# cymometer.net
KiCad netlist of a schematic drawn in Altium Designer
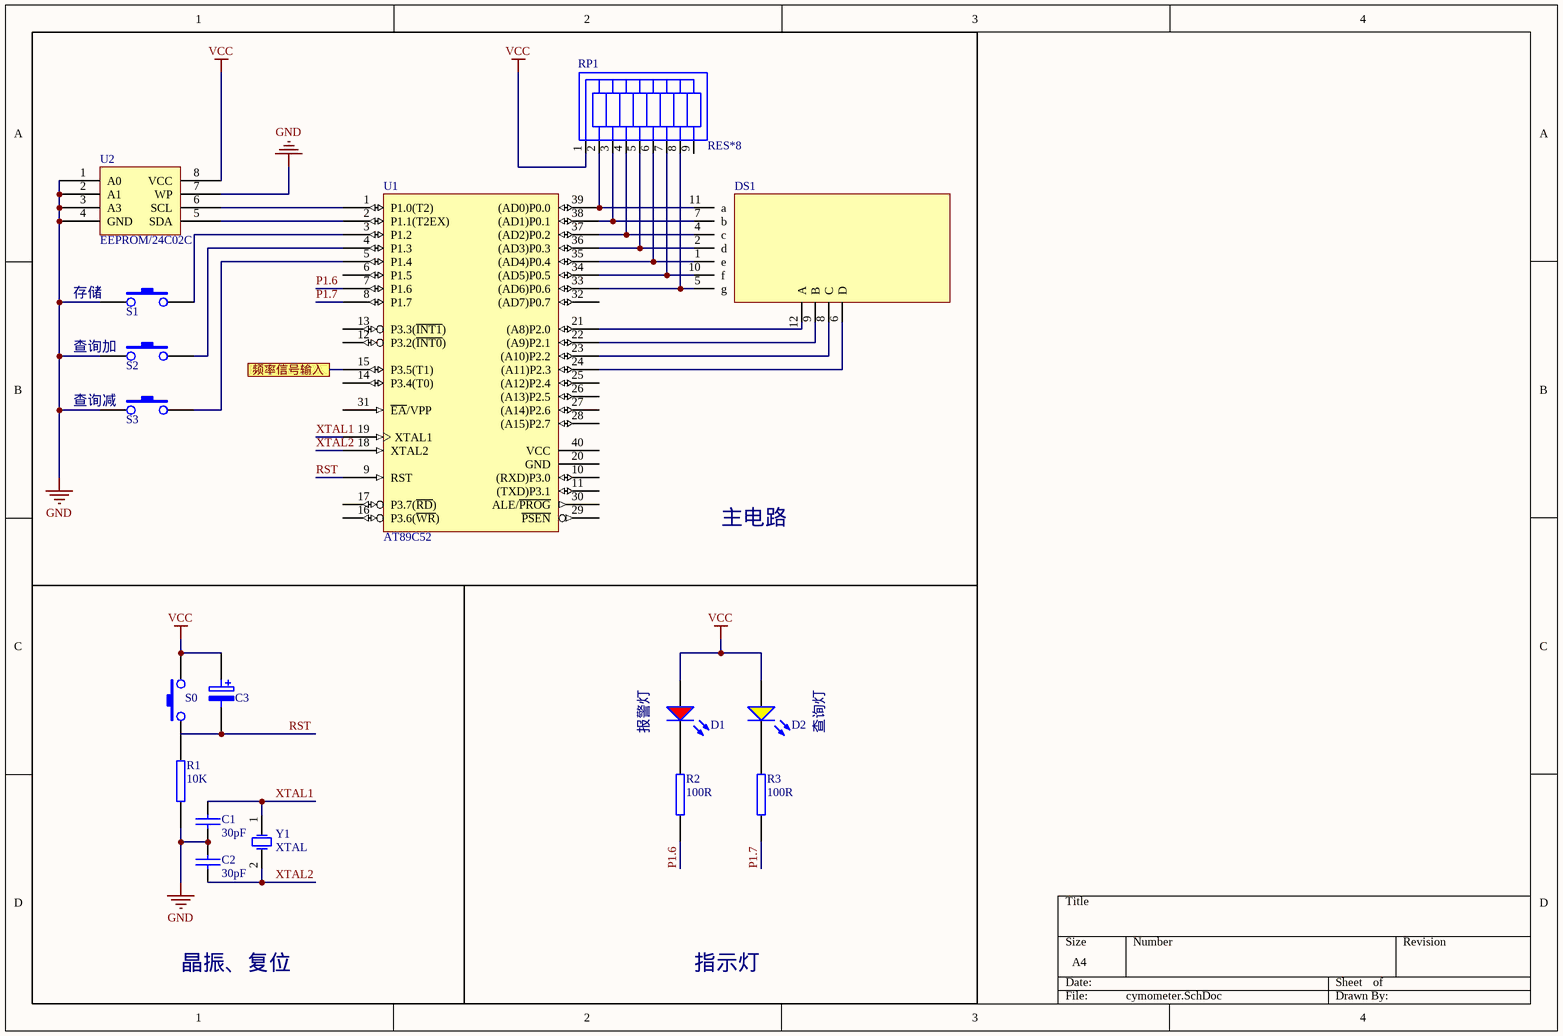
[diagram p0: cymometer.SchDoc]

(export (version "E")
  (design (tool "Eeschema 10.0.6"))
  (components
    (comp (ref "C1") (value "30pF") (description "Capacitor") (libsource (lib "杂元件库") (part "CAP")))
    (comp (ref "C2") (value "30pF") (description "Capacitor") (libsource (lib "杂元件库") (part "CAP")))
    (comp (ref "C3")
      (value "ELECTRO2")
      (description "Electrolytic Capacitor")
      (libsource (lib "杂元件库") (part "ELECTRO2"))
    )
    (comp (ref "D1")
      (value "红灯 0805")
      (footprint "LC-0805_LED_S1")
      (description "发光二极管")
      (libsource (lib "Miscellaneous Devices LC") (part "0805 红灯"))
    )
    (comp (ref "D2")
      (value "黄灯 0805")
      (footprint "LC-0805_LED_S1")
      (description "发光二极管")
      (libsource (lib "Miscellaneous Devices LC") (part "0805 黄灯"))
    )
    (comp (ref "DS1") (value "LED") (footprint "LED-4 - duplicate") (libsource (lib "led数码管") (part "LED-4")))
    (comp (ref "R1") (value "10K") (libsource (lib "杂元件库") (part "RES2")))
    (comp (ref "R2") (value "100R") (libsource (lib "杂元件库") (part "RES2")))
    (comp (ref "R3") (value "100R") (libsource (lib "杂元件库") (part "RES2")))
    (comp (ref "RP1") (value "RES*8") (footprint "SIP9") (libsource (lib "常用1") (part "RES*8")))
    (comp (ref "S0") (value "SW-PB") (libsource (lib "杂元件库") (part "SW-PB")))
    (comp (ref "S1") (value "SW-PB") (libsource (lib "杂元件库") (part "SW-PB")))
    (comp (ref "S2") (value "SW-PB") (libsource (lib "杂元件库") (part "SW-PB")))
    (comp (ref "S3") (value "SW-PB") (libsource (lib "杂元件库") (part "SW-PB")))
    (comp (ref "U1")
      (value "AT89C52")
      (footprint "Dual-In-Line Package:DIP-40")
      (description "8-Bit Microcontroller with 8K Flash ROM")
      (libsource (lib "Atmel Microcontroller 8051 Architecture") (part "AT89C52"))
    )
    (comp (ref "U2")
      (value "EEPROM/24C02C")
      (footprint "LC-SOIC-8_150mil")
      (description "EEPROM")
      (libsource (lib "Miscellaneous Devices LC") (part "EEPROM/AT24C256C-SSHL-T"))
    )
    (comp (ref "Y1") (value "XTAL") (footprint "XTAL") (libsource (lib "XTAL") (part "XTAL")))
  )
  (nets
    (net (code "1") (name "/P1.6") (class "Default")
      (node (ref "R2") (pin "2") (pinfunction "2_2") (pintype "passive"))
      (node (ref "U1") (pin "7") (pinfunction "P1.6_7") (pintype "bidirectional"))
    )
    (net (code "2") (name "/P1.7") (class "Default")
      (node (ref "R3") (pin "2") (pinfunction "2_2") (pintype "passive"))
      (node (ref "U1") (pin "8") (pinfunction "P1.7_8") (pintype "bidirectional"))
    )
    (net (code "3") (name "/RST") (class "Default")
      (node (ref "C3") (pin "2") (pinfunction "2_2") (pintype "passive"))
      (node (ref "R1") (pin "1") (pinfunction "1_1") (pintype "passive"))
      (node (ref "U1") (pin "9") (pinfunction "RST_9") (pintype "input"))
    )
    (net (code "4") (name "/XTAL1") (class "Default")
      (node (ref "C1") (pin "1") (pinfunction "1_1") (pintype "passive"))
      (node (ref "U1") (pin "19") (pinfunction "XTAL1_19") (pintype "input"))
      (node (ref "Y1") (pin "1") (pinfunction "1_1") (pintype "passive"))
    )
    (net (code "5") (name "/XTAL2") (class "Default")
      (node (ref "C2") (pin "2") (pinfunction "2_2") (pintype "passive"))
      (node (ref "U1") (pin "18") (pinfunction "XTAL2_18") (pintype "input"))
      (node (ref "Y1") (pin "2") (pinfunction "2_2") (pintype "passive"))
    )
    (net (code "6") (name "/频率信号输入") (class "Default")
      (node (ref "U1") (pin "15") (pinfunction "P3.5(T1)_15") (pintype "bidirectional"))
    )
    (net (code "7") (name "GND") (class "Default")
      (node (ref "C1") (pin "2") (pinfunction "2_2") (pintype "passive"))
      (node (ref "C2") (pin "1") (pinfunction "1_1") (pintype "passive"))
      (node (ref "R1") (pin "2") (pinfunction "2_2") (pintype "passive"))
      (node (ref "S1") (pin "2") (pinfunction "2_2") (pintype "passive"))
      (node (ref "S2") (pin "2") (pinfunction "2_2") (pintype "passive"))
      (node (ref "S3") (pin "2") (pinfunction "2_2") (pintype "passive"))
      (node (ref "U2") (pin "1") (pinfunction "A0_1") (pintype "passive"))
      (node (ref "U2") (pin "2") (pinfunction "A1_2") (pintype "passive"))
      (node (ref "U2") (pin "3") (pinfunction "A3_3") (pintype "passive"))
      (node (ref "U2") (pin "4") (pinfunction "GND_4") (pintype "passive"))
      (node (ref "U2") (pin "7") (pinfunction "WP_7") (pintype "passive"))
    )
    (net (code "8") (name "Net-(D1-PadK)") (class "Default")
      (node (ref "D1") (pin "K") (pinfunction "K_K") (pintype "passive"))
      (node (ref "R2") (pin "1") (pinfunction "1_1") (pintype "passive"))
    )
    (net (code "9") (name "Net-(D2-PadK)") (class "Default")
      (node (ref "D2") (pin "K") (pinfunction "K_K") (pintype "passive"))
      (node (ref "R3") (pin "1") (pinfunction "1_1") (pintype "passive"))
    )
    (net (code "10") (name "Net-(DS1-A)") (class "Default")
      (node (ref "DS1") (pin "12") (pinfunction "A_12") (pintype "passive"))
      (node (ref "U1") (pin "21") (pinfunction "(A8)P2.0_21") (pintype "bidirectional"))
    )
    (net (code "11") (name "Net-(DS1-B)") (class "Default")
      (node (ref "DS1") (pin "9") (pinfunction "B_9") (pintype "passive"))
      (node (ref "U1") (pin "22") (pinfunction "(A9)P2.1_22") (pintype "bidirectional"))
    )
    (net (code "12") (name "Net-(DS1-C)") (class "Default")
      (node (ref "DS1") (pin "8") (pinfunction "C_8") (pintype "passive"))
      (node (ref "U1") (pin "23") (pinfunction "(A10)P2.2_23") (pintype "bidirectional"))
    )
    (net (code "13") (name "Net-(DS1-D)") (class "Default")
      (node (ref "DS1") (pin "6") (pinfunction "D_6") (pintype "passive"))
      (node (ref "U1") (pin "24") (pinfunction "(A11)P2.3_24") (pintype "bidirectional"))
    )
    (net (code "14") (name "Net-(DS1-a)") (class "Default")
      (node (ref "DS1") (pin "11") (pinfunction "a_11") (pintype "passive"))
      (node (ref "RP1") (pin "2") (pintype "passive"))
      (node (ref "U1") (pin "39") (pinfunction "(AD0)P0.0_39") (pintype "bidirectional"))
    )
    (net (code "15") (name "Net-(DS1-b)") (class "Default")
      (node (ref "DS1") (pin "7") (pinfunction "b_7") (pintype "passive"))
      (node (ref "RP1") (pin "3") (pintype "passive"))
      (node (ref "U1") (pin "38") (pinfunction "(AD1)P0.1_38") (pintype "bidirectional"))
    )
    (net (code "16") (name "Net-(DS1-c)") (class "Default")
      (node (ref "DS1") (pin "4") (pinfunction "c_4") (pintype "passive"))
      (node (ref "RP1") (pin "4") (pintype "passive"))
      (node (ref "U1") (pin "37") (pinfunction "(AD2)P0.2_37") (pintype "bidirectional"))
    )
    (net (code "17") (name "Net-(DS1-d)") (class "Default")
      (node (ref "DS1") (pin "2") (pinfunction "d_2") (pintype "passive"))
      (node (ref "RP1") (pin "5") (pintype "passive"))
      (node (ref "U1") (pin "36") (pinfunction "(AD3)P0.3_36") (pintype "bidirectional"))
    )
    (net (code "18") (name "Net-(DS1-e)") (class "Default")
      (node (ref "DS1") (pin "1") (pinfunction "e_1") (pintype "passive"))
      (node (ref "RP1") (pin "6") (pintype "passive"))
      (node (ref "U1") (pin "35") (pinfunction "(AD4)P0.4_35") (pintype "bidirectional"))
    )
    (net (code "19") (name "Net-(DS1-f)") (class "Default")
      (node (ref "DS1") (pin "10") (pinfunction "f_10") (pintype "passive"))
      (node (ref "RP1") (pin "7") (pintype "passive"))
      (node (ref "U1") (pin "34") (pinfunction "(AD5)P0.5_34") (pintype "bidirectional"))
    )
    (net (code "20") (name "Net-(DS1-g)") (class "Default")
      (node (ref "DS1") (pin "5") (pinfunction "g_5") (pintype "passive"))
      (node (ref "RP1") (pin "8") (pintype "passive"))
      (node (ref "U1") (pin "33") (pinfunction "(AD6)P0.6_33") (pintype "bidirectional"))
    )
    (net (code "21") (name "Net-(U1-P1.0(T2))") (class "Default")
      (node (ref "U1") (pin "1") (pinfunction "P1.0(T2)_1") (pintype "bidirectional"))
      (node (ref "U2") (pin "6") (pinfunction "SCL_6") (pintype "passive"))
    )
    (net (code "22") (name "Net-(U1-P1.1(T2EX))") (class "Default")
      (node (ref "U1") (pin "2") (pinfunction "P1.1(T2EX)_2") (pintype "bidirectional"))
      (node (ref "U2") (pin "5") (pinfunction "SDA_5") (pintype "passive"))
    )
    (net (code "23") (name "Net-(U1-P1.2)") (class "Default")
      (node (ref "S1") (pin "1") (pinfunction "1_1") (pintype "passive"))
      (node (ref "U1") (pin "3") (pinfunction "P1.2_3") (pintype "bidirectional"))
    )
    (net (code "24") (name "Net-(U1-P1.3)") (class "Default")
      (node (ref "S2") (pin "1") (pinfunction "1_1") (pintype "passive"))
      (node (ref "U1") (pin "4") (pinfunction "P1.3_4") (pintype "bidirectional"))
    )
    (net (code "25") (name "Net-(U1-P1.4)") (class "Default")
      (node (ref "S3") (pin "1") (pinfunction "1_1") (pintype "passive"))
      (node (ref "U1") (pin "5") (pinfunction "P1.4_5") (pintype "bidirectional"))
    )
    (net (code "26") (name "VCC") (class "Default")
      (node (ref "C3") (pin "1") (pinfunction "1_1") (pintype "passive"))
      (node (ref "D1") (pin "A") (pinfunction "A_A") (pintype "passive"))
      (node (ref "D2") (pin "A") (pinfunction "A_A") (pintype "passive"))
      (node (ref "RP1") (pin "1") (pintype "passive"))
      (node (ref "S0") (pin "1") (pinfunction "1_1") (pintype "passive"))
      (node (ref "U2") (pin "8") (pinfunction "VCC_8") (pintype "passive"))
    )
    (net (code "27") (name "unconnected-(RP1-Pad9)") (class "Default")
      (node (ref "RP1") (pin "9") (pintype "passive"))
    )
    (net (code "28") (name "unconnected-(S0-Pad2)") (class "Default")
      (node (ref "S0") (pin "2") (pinfunction "2_2") (pintype "passive"))
    )
    (net (code "29") (name "unconnected-(U1-(A12)P2.4-Pad25)") (class "Default")
      (node (ref "U1") (pin "25") (pinfunction "(A12)P2.4_25") (pintype "bidirectional"))
    )
    (net (code "30") (name "unconnected-(U1-(A13)P2.5-Pad26)") (class "Default")
      (node (ref "U1") (pin "26") (pinfunction "(A13)P2.5_26") (pintype "bidirectional"))
    )
    (net (code "31") (name "unconnected-(U1-(A14)P2.6-Pad27)") (class "Default")
      (node (ref "U1") (pin "27") (pinfunction "(A14)P2.6_27") (pintype "bidirectional"))
    )
    (net (code "32") (name "unconnected-(U1-(A15)P2.7-Pad28)") (class "Default")
      (node (ref "U1") (pin "28") (pinfunction "(A15)P2.7_28") (pintype "bidirectional"))
    )
    (net (code "33") (name "unconnected-(U1-(AD7)P0.7-Pad32)") (class "Default")
      (node (ref "U1") (pin "32") (pinfunction "(AD7)P0.7_32") (pintype "bidirectional"))
    )
    (net (code "34") (name "unconnected-(U1-(RXD)P3.0-Pad10)") (class "Default")
      (node (ref "U1") (pin "10") (pinfunction "(RXD)P3.0_10") (pintype "bidirectional"))
    )
    (net (code "35") (name "unconnected-(U1-(TXD)P3.1-Pad11)") (class "Default")
      (node (ref "U1") (pin "11") (pinfunction "(TXD)P3.1_11") (pintype "bidirectional"))
    )
    (net (code "36") (name "unconnected-(U1-ALE{slash}~{PROG}-Pad30)") (class "Default")
      (node (ref "U1") (pin "30") (pinfunction "ALE/~{PROG}_30") (pintype "output"))
    )
    (net (code "37") (name "unconnected-(U1-GND-Pad20)") (class "Default")
      (node (ref "U1") (pin "20") (pinfunction "GND_20") (pintype "power_in"))
    )
    (net (code "38") (name "unconnected-(U1-P1.5-Pad6)") (class "Default")
      (node (ref "U1") (pin "6") (pinfunction "P1.5_6") (pintype "bidirectional"))
    )
    (net (code "39") (name "unconnected-(U1-P3.2(~{INT0})-Pad12)") (class "Default")
      (node (ref "U1") (pin "12") (pinfunction "P3.2(~{INT0})_12") (pintype "bidirectional"))
    )
    (net (code "40") (name "unconnected-(U1-P3.3(~{INT1})-Pad13)") (class "Default")
      (node (ref "U1") (pin "13") (pinfunction "P3.3(~{INT1})_13") (pintype "bidirectional"))
    )
    (net (code "41") (name "unconnected-(U1-P3.4(T0)-Pad14)") (class "Default")
      (node (ref "U1") (pin "14") (pinfunction "P3.4(T0)_14") (pintype "bidirectional"))
    )
    (net (code "42") (name "unconnected-(U1-P3.6(~{WR})-Pad16)") (class "Default")
      (node (ref "U1") (pin "16") (pinfunction "P3.6(~{WR})_16") (pintype "bidirectional"))
    )
    (net (code "43") (name "unconnected-(U1-P3.7(~{RD})-Pad17)") (class "Default")
      (node (ref "U1") (pin "17") (pinfunction "P3.7(~{RD})_17") (pintype "bidirectional"))
    )
    (net (code "44") (name "unconnected-(U1-VCC-Pad40)") (class "Default")
      (node (ref "U1") (pin "40") (pinfunction "VCC_40") (pintype "power_in"))
    )
    (net (code "45") (name "unconnected-(U1-~{EA}{slash}VPP-Pad31)") (class "Default")
      (node (ref "U1") (pin "31") (pinfunction "~{EA}/VPP_31") (pintype "input"))
    )
    (net (code "46") (name "unconnected-(U1-~{PSEN}-Pad29)") (class "Default")
      (node (ref "U1") (pin "29") (pinfunction "~{PSEN}_29") (pintype "output"))
    )
  )
)
